# BpodFSM_r2_0.net
KiCad netlist of a schematic drawn in EAGLE
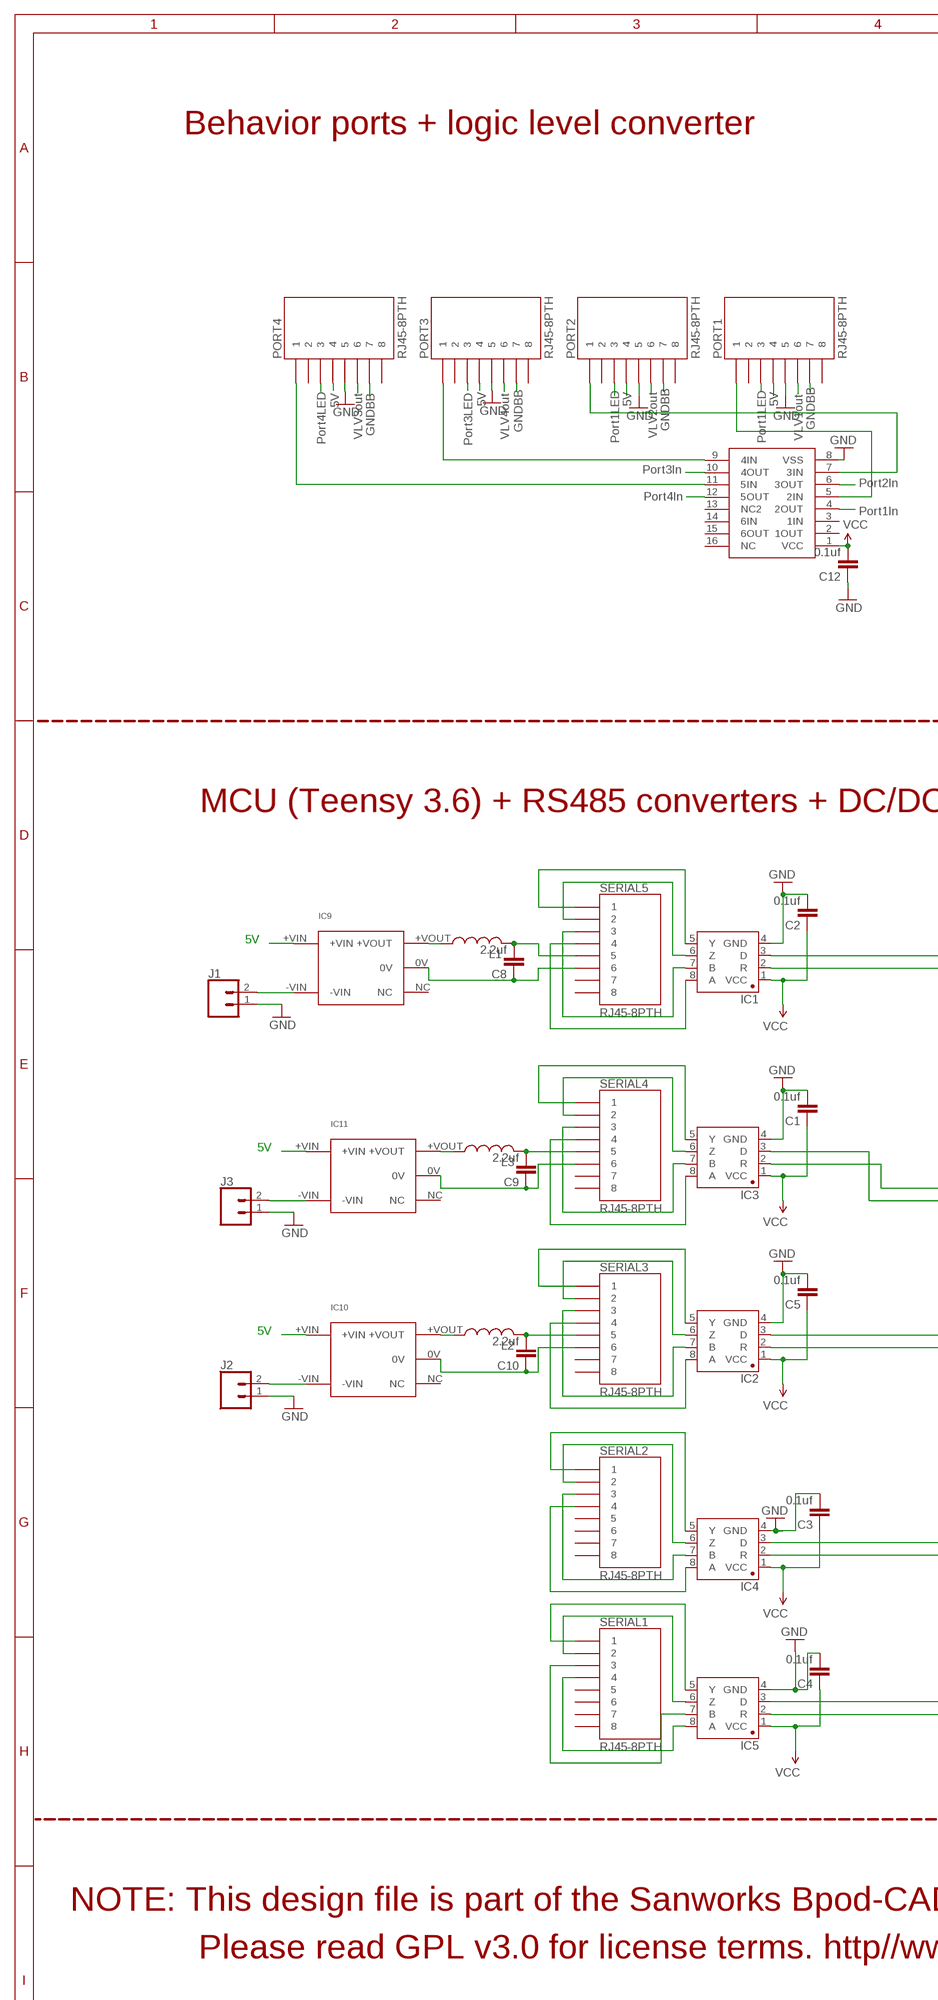
[diagram p0: schematic, sheet 1, part 1 of 2]
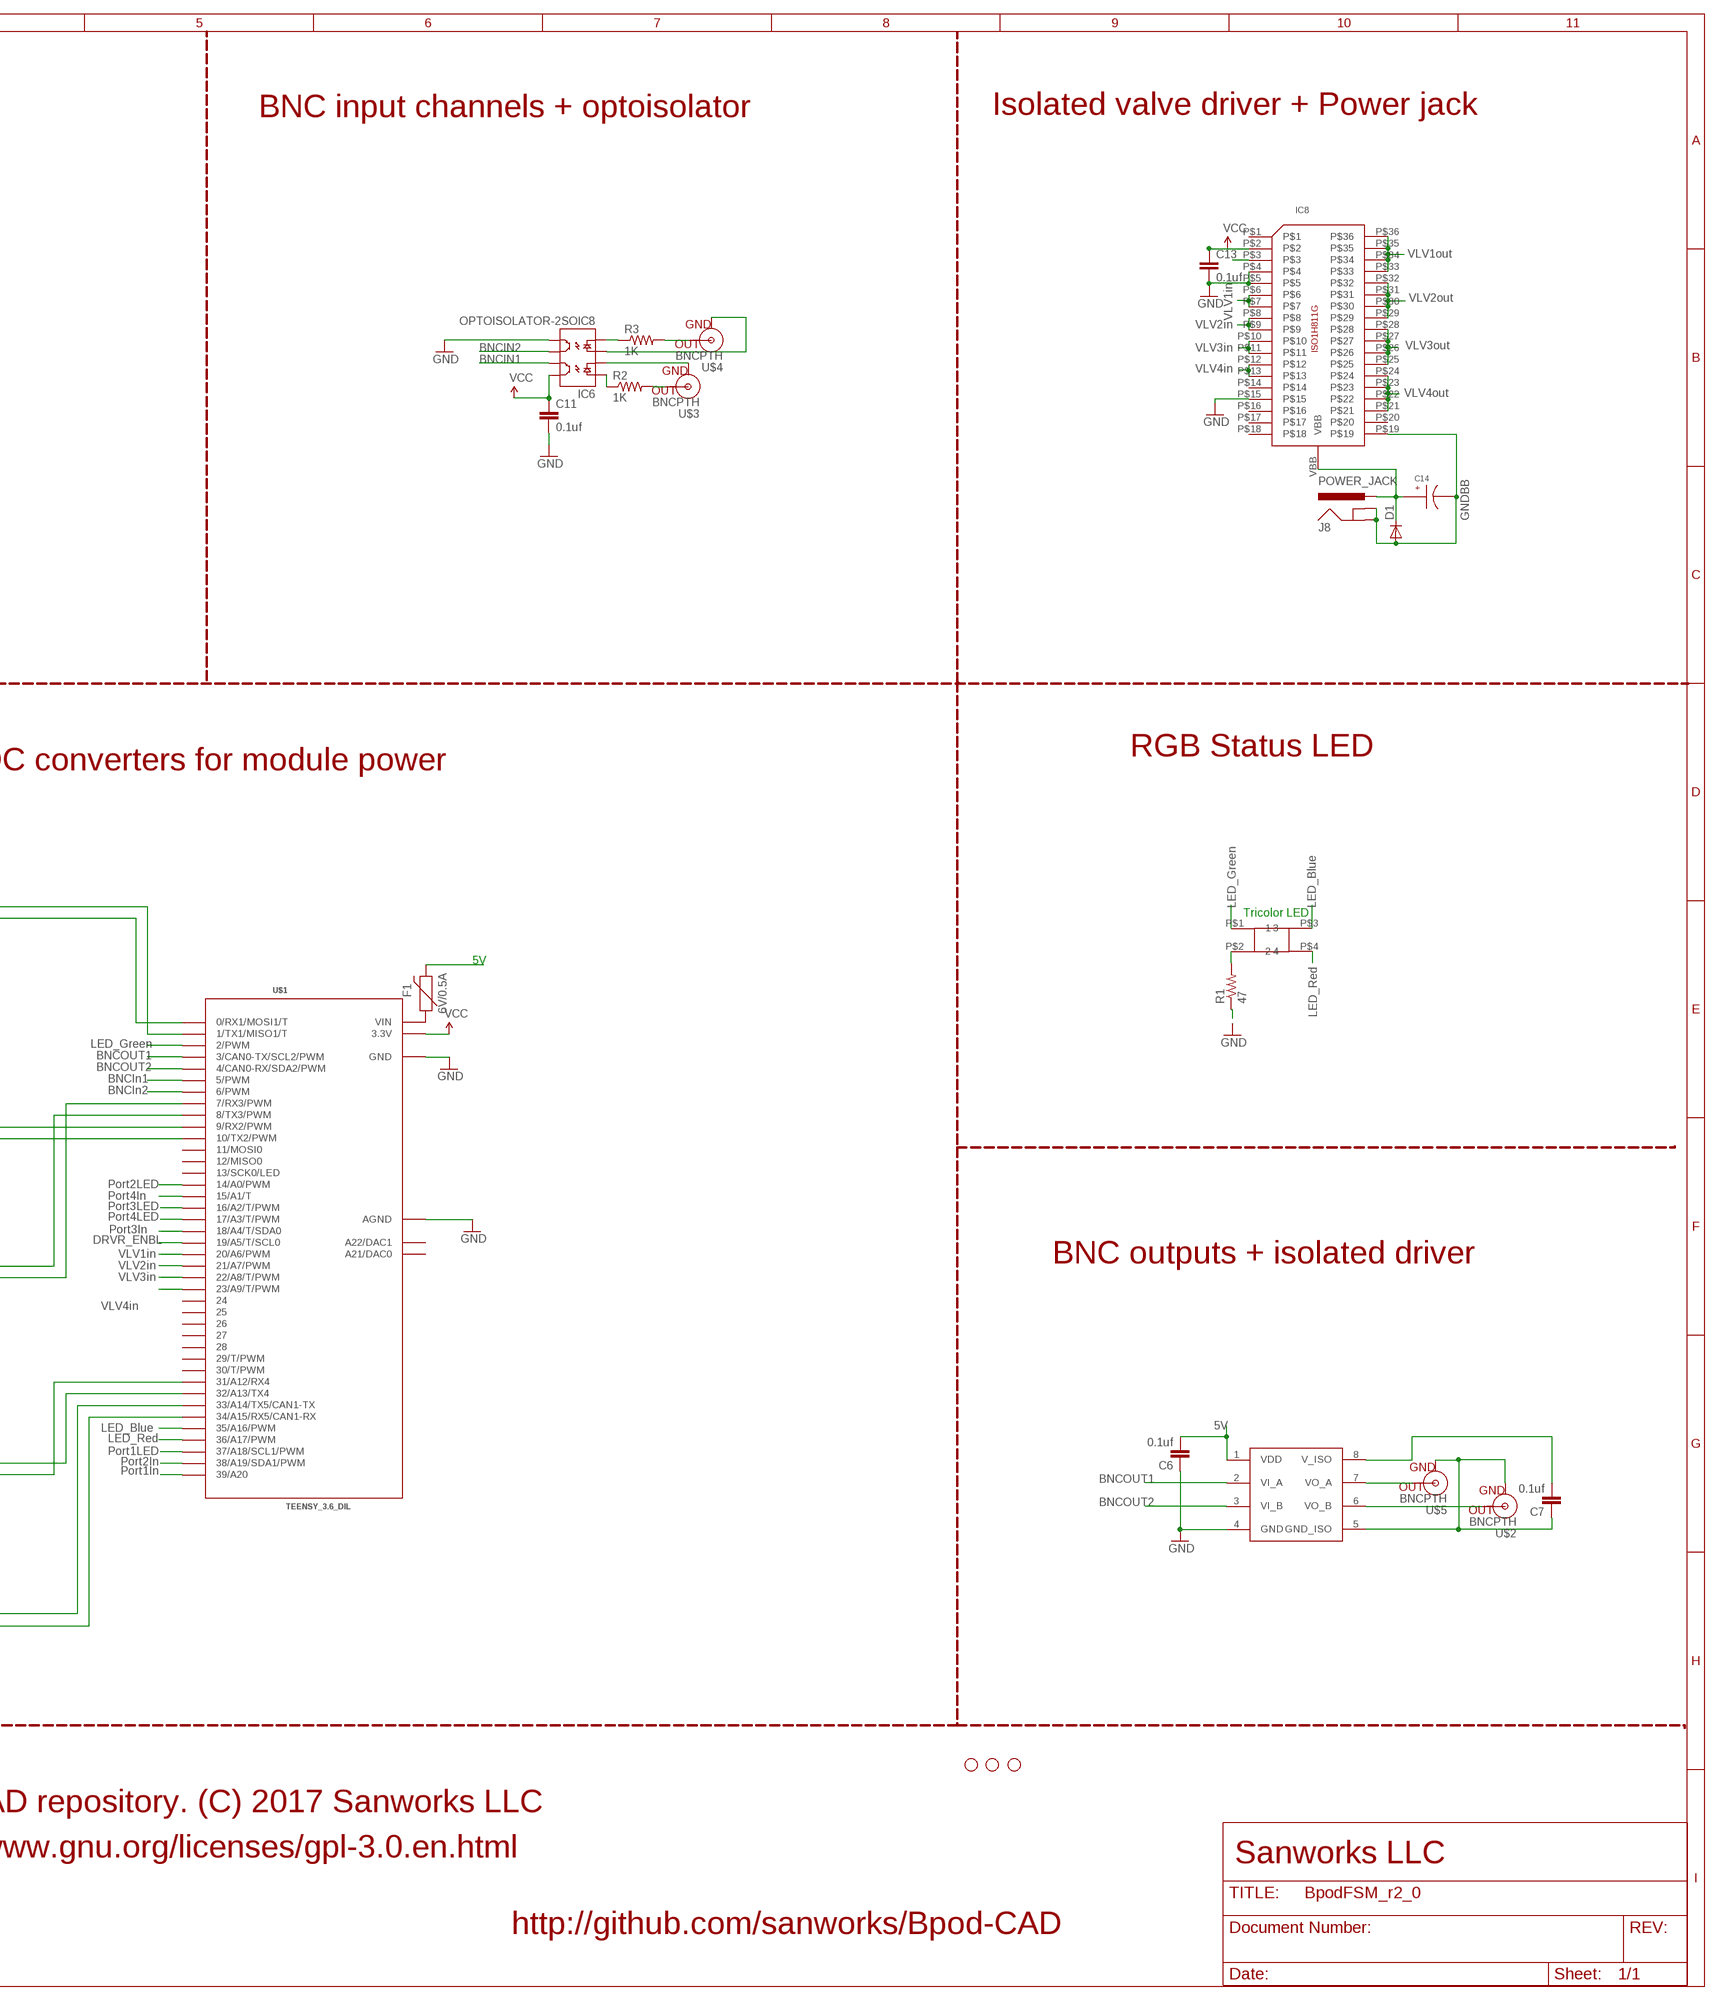
[diagram p1: schematic, sheet 1, part 2 of 2]

(export (version "E")
  (design (tool "Eeschema 10.0.6"))
  (components
    (comp (ref "C1")
      (value "0.1uf")
      (footprint "eagle-import:1206")
      (libsource (lib "eagle-import") (part "CAP1206"))
    )
    (comp (ref "C2")
      (value "0.1uf")
      (footprint "eagle-import:1206")
      (libsource (lib "eagle-import") (part "CAP1206"))
    )
    (comp (ref "C3")
      (value "0.1uf")
      (footprint "eagle-import:1206")
      (libsource (lib "eagle-import") (part "CAP1206"))
    )
    (comp (ref "C4")
      (value "0.1uf")
      (footprint "eagle-import:1206")
      (libsource (lib "eagle-import") (part "CAP1206"))
    )
    (comp (ref "C5")
      (value "0.1uf")
      (footprint "eagle-import:1206")
      (libsource (lib "eagle-import") (part "CAP1206"))
    )
    (comp (ref "C6")
      (value "0.1uf")
      (footprint "eagle-import:1206")
      (libsource (lib "eagle-import") (part "CAP1206"))
    )
    (comp (ref "C7")
      (value "0.1uf")
      (footprint "eagle-import:1206")
      (libsource (lib "eagle-import") (part "CAP1206"))
    )
    (comp (ref "C8")
      (value "2.2uf")
      (footprint "eagle-import:1206")
      (libsource (lib "eagle-import") (part "CAP1206"))
    )
    (comp (ref "C9")
      (value "2.2uf")
      (footprint "eagle-import:1206")
      (libsource (lib "eagle-import") (part "CAP1206"))
    )
    (comp (ref "C10")
      (value "2.2uf")
      (footprint "eagle-import:1206")
      (libsource (lib "eagle-import") (part "CAP1206"))
    )
    (comp (ref "C11")
      (value "0.1uf")
      (footprint "eagle-import:1206")
      (libsource (lib "eagle-import") (part "CAP1206"))
    )
    (comp (ref "C12")
      (value "0.1uf")
      (footprint "eagle-import:1206")
      (libsource (lib "eagle-import") (part "CAP1206"))
    )
    (comp (ref "C13")
      (value "0.1uf")
      (footprint "eagle-import:1206")
      (libsource (lib "eagle-import") (part "CAP1206"))
    )
    (comp (ref "C14")
      (value "EEE-FK1H100UR")
      (footprint "eagle-import:EEE-FK1H100UR")
      (libsource (lib "eagle-import") (part "EEE-FK1H100UR"))
    )
    (comp (ref "D1")
      (value "DIODE-DO214AA")
      (footprint "eagle-import:DO214AA")
      (libsource (lib "eagle-import") (part "DIODE-DO214AA"))
    )
    (comp (ref "F1")
      (value "6V/0.5A")
      (footprint "eagle-import:1206")
      (libsource (lib "eagle-import") (part "PPTC_HALF-AMP"))
    )
    (comp (ref "IC1")
      (value "SN65HVD31DR")
      (footprint "eagle-import:SO08")
      (libsource (lib "eagle-import") (part "SN65HVD31DR"))
    )
    (comp (ref "IC2")
      (value "SN65HVD31DR")
      (footprint "eagle-import:SO08")
      (libsource (lib "eagle-import") (part "SN65HVD31DR"))
    )
    (comp (ref "IC3")
      (value "SN65HVD31DR")
      (footprint "eagle-import:SO08")
      (libsource (lib "eagle-import") (part "SN65HVD31DR"))
    )
    (comp (ref "IC4")
      (value "SN65HVD31DR")
      (footprint "eagle-import:SO08")
      (libsource (lib "eagle-import") (part "SN65HVD31DR"))
    )
    (comp (ref "IC5")
      (value "SN65HVD31DR")
      (footprint "eagle-import:SO08")
      (libsource (lib "eagle-import") (part "SN65HVD31DR"))
    )
    (comp (ref "IC6")
      (value "OPTOISOLATOR-2SOIC8")
      (footprint "eagle-import:SO08-2")
      (libsource (lib "eagle-import") (part "OPTOISOLATOR-2SOIC8"))
    )
    (comp (ref "IC7")
      (value "ADUM5240")
      (footprint "eagle-import:SO08")
      (libsource (lib "eagle-import") (part "ADUM5240"))
    )
    (comp (ref "IC8")
      (value "ISO1H811G")
      (footprint "eagle-import:ISO1H811G")
      (libsource (lib "eagle-import") (part "ISO1H811G"))
    )
    (comp (ref "IC9")
      (value "MTU1D0505MC")
      (footprint "eagle-import:MTU1D0505MC")
      (libsource (lib "eagle-import") (part "MTU1D0505MC"))
    )
    (comp (ref "IC10")
      (value "MTU1D0505MC")
      (footprint "eagle-import:MTU1D0505MC")
      (libsource (lib "eagle-import") (part "MTU1D0505MC"))
    )
    (comp (ref "IC11")
      (value "MTU1D0505MC")
      (footprint "eagle-import:MTU1D0505MC")
      (libsource (lib "eagle-import") (part "MTU1D0505MC"))
    )
    (comp (ref "IC12")
      (value "CD4050")
      (footprint "eagle-import:SO16")
      (libsource (lib "eagle-import") (part "CD4050"))
    )
    (comp (ref "J1")
      (value "CONN_02")
      (footprint "eagle-import:1X02")
      (libsource (lib "eagle-import") (part "CONN_02"))
    )
    (comp (ref "J2")
      (value "CONN_02")
      (footprint "eagle-import:1X02")
      (libsource (lib "eagle-import") (part "CONN_02"))
    )
    (comp (ref "J3")
      (value "CONN_02")
      (footprint "eagle-import:1X02")
      (libsource (lib "eagle-import") (part "CONN_02"))
    )
    (comp (ref "J8")
      (value "POWER_JACK")
      (footprint "eagle-import:POWER_JACK_PTH")
      (libsource (lib "eagle-import") (part "POWER_JACK"))
    )
    (comp (ref "JP3")
      (value "STAND-OFF")
      (footprint "eagle-import:STAND-OFF")
      (libsource (lib "eagle-import") (part "STAND-OFF"))
    )
    (comp (ref "JP4")
      (value "STAND-OFF")
      (footprint "eagle-import:STAND-OFF")
      (libsource (lib "eagle-import") (part "STAND-OFF"))
    )
    (comp (ref "JP5")
      (value "STAND-OFF")
      (footprint "eagle-import:STAND-OFF")
      (libsource (lib "eagle-import") (part "STAND-OFF"))
    )
    (comp (ref "L1")
      (value "L-USL3225M")
      (footprint "eagle-import:L3225M")
      (libsource (lib "eagle-import") (part "L-USL3225M"))
    )
    (comp (ref "L2")
      (value "L-USL3225M")
      (footprint "eagle-import:L3225M")
      (libsource (lib "eagle-import") (part "L-USL3225M"))
    )
    (comp (ref "L3")
      (value "L-USL3225M")
      (footprint "eagle-import:L3225M")
      (libsource (lib "eagle-import") (part "L-USL3225M"))
    )
    (comp (ref "PORT1")
      (value "RJ45-8PTH")
      (footprint "eagle-import:RJ45-8")
      (libsource (lib "eagle-import") (part "RJ45-8PTH"))
    )
    (comp (ref "PORT2")
      (value "RJ45-8PTH")
      (footprint "eagle-import:RJ45-8")
      (libsource (lib "eagle-import") (part "RJ45-8PTH"))
    )
    (comp (ref "PORT3")
      (value "RJ45-8PTH")
      (footprint "eagle-import:RJ45-8")
      (libsource (lib "eagle-import") (part "RJ45-8PTH"))
    )
    (comp (ref "PORT4")
      (value "RJ45-8PTH")
      (footprint "eagle-import:RJ45-8")
      (libsource (lib "eagle-import") (part "RJ45-8PTH"))
    )
    (comp (ref "R1")
      (value "47")
      (footprint "eagle-import:1206")
      (libsource (lib "eagle-import") (part "RESISTOR1206"))
    )
    (comp (ref "R2")
      (value "1K")
      (footprint "eagle-import:1206")
      (libsource (lib "eagle-import") (part "SparkFun-Resistors_RESISTOR1206"))
    )
    (comp (ref "R3")
      (value "1K")
      (footprint "eagle-import:1206")
      (libsource (lib "eagle-import") (part "SparkFun-Resistors_RESISTOR1206"))
    )
    (comp (ref "SERIAL1")
      (value "RJ45-8PTH")
      (footprint "eagle-import:RJ45-8")
      (libsource (lib "eagle-import") (part "RJ45-8PTH"))
    )
    (comp (ref "SERIAL2")
      (value "RJ45-8PTH")
      (footprint "eagle-import:RJ45-8")
      (libsource (lib "eagle-import") (part "RJ45-8PTH"))
    )
    (comp (ref "SERIAL3")
      (value "RJ45-8PTH")
      (footprint "eagle-import:RJ45-8")
      (libsource (lib "eagle-import") (part "RJ45-8PTH"))
    )
    (comp (ref "SERIAL4")
      (value "RJ45-8PTH")
      (footprint "eagle-import:RJ45-8")
      (libsource (lib "eagle-import") (part "RJ45-8PTH"))
    )
    (comp (ref "SERIAL5")
      (value "RJ45-8PTH")
      (footprint "eagle-import:RJ45-8")
      (libsource (lib "eagle-import") (part "RJ45-8PTH"))
    )
    (comp (ref "U$1")
      (value "TEENSY_3.6_DIL")
      (footprint "eagle-import:TEENSY_3.6_DIL")
      (libsource (lib "eagle-import") (part "TEENSY_3.6_DIL"))
    )
    (comp (ref "U$2")
      (value "BNCPTH")
      (footprint "eagle-import:BNC")
      (libsource (lib "eagle-import") (part "BNCPTH"))
    )
    (comp (ref "U$3")
      (value "BNCPTH")
      (footprint "eagle-import:BNC")
      (libsource (lib "eagle-import") (part "BNCPTH"))
    )
    (comp (ref "U$4")
      (value "BNCPTH")
      (footprint "eagle-import:BNC")
      (libsource (lib "eagle-import") (part "BNCPTH"))
    )
    (comp (ref "U$5")
      (value "BNCPTH")
      (footprint "eagle-import:BNC")
      (libsource (lib "eagle-import") (part "BNCPTH"))
    )
    (comp (ref "U$8")
      (value "SQUARE_TRICOLOR_LED")
      (footprint "eagle-import:SQUARE_TRICOLOR_LED")
      (libsource (lib "eagle-import") (part "SQUARE_TRICOLOR_LED"))
    )
  )
  (nets
    (net (code "1") (name "/5V") (class "Default")
      (node (ref "C6") (pin "2") (pinfunction "2_2") (pintype "passive"))
      (node (ref "F1") (pin "2") (pinfunction "2_2") (pintype "bidirectional"))
      (node (ref "IC10") (pin "+VIN") (pinfunction "+VIN_+VIN") (pintype "bidirectional"))
      (node (ref "IC11") (pin "+VIN") (pinfunction "+VIN_+VIN") (pintype "bidirectional"))
      (node (ref "IC7") (pin "1") (pinfunction "VDD_1") (pintype "bidirectional"))
      (node (ref "IC9") (pin "+VIN") (pinfunction "+VIN_+VIN") (pintype "bidirectional"))
      (node (ref "PORT1") (pin "4") (pinfunction "4_4") (pintype "bidirectional"))
      (node (ref "PORT2") (pin "4") (pinfunction "4_4") (pintype "bidirectional"))
      (node (ref "PORT3") (pin "4") (pinfunction "4_4") (pintype "bidirectional"))
      (node (ref "PORT4") (pin "4") (pinfunction "4_4") (pintype "bidirectional"))
    )
    (net (code "2") (name "/BNCIN1") (class "Default")
      (node (ref "IC6") (pin "7") (pinfunction "EM1_7") (pintype "bidirectional"))
      (node (ref "U$1") (pin "6") (pinfunction "6/PWM_6") (pintype "bidirectional"))
    )
    (net (code "3") (name "/BNCIN2") (class "Default")
      (node (ref "IC6") (pin "6") (pinfunction "CL2_6") (pintype "bidirectional"))
      (node (ref "U$1") (pin "5") (pinfunction "5/PWM_5") (pintype "bidirectional"))
    )
    (net (code "4") (name "/BNCOUT1") (class "Default")
      (node (ref "IC7") (pin "3") (pinfunction "VI_B_3") (pintype "bidirectional"))
      (node (ref "U$1") (pin "4") (pinfunction "4/CAN0-RX/SDA2/PWM_4") (pintype "bidirectional"))
    )
    (net (code "5") (name "/BNCOUT2") (class "Default")
      (node (ref "IC7") (pin "2") (pinfunction "VI_A_2") (pintype "bidirectional"))
      (node (ref "U$1") (pin "3") (pinfunction "3/CAN0-TX/SCL2/PWM_3") (pintype "bidirectional"))
    )
    (net (code "6") (name "/DRVR_ENBL") (class "Default")
      (node (ref "IC8") (pin "P$3") (pinfunction "P$3_P$3") (pintype "bidirectional"))
      (node (ref "U$1") (pin "19/A5") (pinfunction "19/A5/T/SCL0_19/A5") (pintype "bidirectional"))
    )
    (net (code "7") (name "/GNDBB") (class "Default")
      (node (ref "C14") (pin "CATHODE") (pinfunction "CATHODE_CATHODE") (pintype "bidirectional"))
      (node (ref "D1") (pin "A") (pinfunction "A_A") (pintype "passive"))
      (node (ref "IC8") (pin "P$19") (pinfunction "P$19_P$19") (pintype "bidirectional"))
      (node (ref "J8") (pin "GND") (pinfunction "GND_GND") (pintype "bidirectional"))
      (node (ref "J8") (pin "GNDBREAK") (pinfunction "GNDBREAK_GNDBREAK") (pintype "bidirectional"))
      (node (ref "PORT1") (pin "7") (pinfunction "7_7") (pintype "bidirectional"))
      (node (ref "PORT2") (pin "7") (pinfunction "7_7") (pintype "bidirectional"))
      (node (ref "PORT3") (pin "7") (pinfunction "7_7") (pintype "bidirectional"))
      (node (ref "PORT4") (pin "7") (pinfunction "7_7") (pintype "bidirectional"))
    )
    (net (code "8") (name "/LED_BLUE") (class "Default")
      (node (ref "U$1") (pin "35/A16") (pinfunction "35/A16/PWM_35/A16") (pintype "bidirectional"))
      (node (ref "U$8") (pin "P$3") (pinfunction "3_P$3") (pintype "bidirectional"))
    )
    (net (code "9") (name "/LED_GREEN") (class "Default")
      (node (ref "U$1") (pin "2") (pinfunction "2/PWM_2") (pintype "bidirectional"))
      (node (ref "U$8") (pin "P$1") (pinfunction "1_P$1") (pintype "bidirectional"))
    )
    (net (code "10") (name "/LED_RED") (class "Default")
      (node (ref "U$1") (pin "36/A17") (pinfunction "36/A17/PWM_36/A17") (pintype "bidirectional"))
      (node (ref "U$8") (pin "P$4") (pinfunction "4_P$4") (pintype "bidirectional"))
    )
    (net (code "11") (name "/PORT1IN") (class "Default")
      (node (ref "IC12") (pin "4") (pinfunction "2OUT_4") (pintype "bidirectional"))
      (node (ref "U$1") (pin "39/A20") (pinfunction "39/A20_39/A20") (pintype "bidirectional"))
    )
    (net (code "12") (name "/PORT1LED") (class "Default")
      (node (ref "PORT1") (pin "3") (pinfunction "3_3") (pintype "bidirectional"))
      (node (ref "U$1") (pin "37/A18") (pinfunction "37/A18/SCL1/PWM_37/A18") (pintype "bidirectional"))
    )
    (net (code "13") (name "/PORT2IN") (class "Default")
      (node (ref "IC12") (pin "6") (pinfunction "3OUT_6") (pintype "bidirectional"))
      (node (ref "U$1") (pin "38/A19") (pinfunction "38/A19/SDA1/PWM_38/A19") (pintype "bidirectional"))
    )
    (net (code "14") (name "/PORT2LED") (class "Default")
      (node (ref "PORT2") (pin "3") (pinfunction "3_3") (pintype "bidirectional"))
      (node (ref "U$1") (pin "14/A0") (pinfunction "14/A0/PWM_14/A0") (pintype "bidirectional"))
    )
    (net (code "15") (name "/PORT3IN") (class "Default")
      (node (ref "IC12") (pin "10") (pinfunction "4OUT_10") (pintype "bidirectional"))
      (node (ref "U$1") (pin "18/A4") (pinfunction "18/A4/T/SDA0_18/A4") (pintype "bidirectional"))
    )
    (net (code "16") (name "/PORT3LED") (class "Default")
      (node (ref "PORT3") (pin "3") (pinfunction "3_3") (pintype "bidirectional"))
      (node (ref "U$1") (pin "16/A2") (pinfunction "16/A2/T/PWM_16/A2") (pintype "bidirectional"))
    )
    (net (code "17") (name "/PORT4IN") (class "Default")
      (node (ref "IC12") (pin "12") (pinfunction "5OUT_12") (pintype "bidirectional"))
      (node (ref "U$1") (pin "15/A1") (pinfunction "15/A1/T_15/A1") (pintype "bidirectional"))
    )
    (net (code "18") (name "/PORT4LED") (class "Default")
      (node (ref "PORT4") (pin "3") (pinfunction "3_3") (pintype "bidirectional"))
      (node (ref "U$1") (pin "17/A3") (pinfunction "17/A3/T/PWM_17/A3") (pintype "bidirectional"))
    )
    (net (code "19") (name "/VLV1IN") (class "Default")
      (node (ref "IC8") (pin "P$6") (pinfunction "P$6_P$6") (pintype "bidirectional"))
      (node (ref "IC8") (pin "P$7") (pinfunction "P$7_P$7") (pintype "bidirectional"))
      (node (ref "U$1") (pin "23/A9") (pinfunction "23/A9/T/PWM_23/A9") (pintype "bidirectional"))
    )
    (net (code "20") (name "/VLV1OUT") (class "Default")
      (node (ref "IC8") (pin "P$33") (pinfunction "P$33_P$33") (pintype "bidirectional"))
      (node (ref "IC8") (pin "P$34") (pinfunction "P$34_P$34") (pintype "bidirectional"))
      (node (ref "IC8") (pin "P$35") (pinfunction "P$35_P$35") (pintype "bidirectional"))
      (node (ref "IC8") (pin "P$36") (pinfunction "P$36_P$36") (pintype "bidirectional"))
      (node (ref "PORT1") (pin "6") (pinfunction "6_6") (pintype "bidirectional"))
    )
    (net (code "21") (name "/VLV2IN") (class "Default")
      (node (ref "IC8") (pin "P$8") (pinfunction "P$8_P$8") (pintype "bidirectional"))
      (node (ref "IC8") (pin "P$9") (pinfunction "P$9_P$9") (pintype "bidirectional"))
      (node (ref "U$1") (pin "22/A8") (pinfunction "22/A8/T/PWM_22/A8") (pintype "bidirectional"))
    )
    (net (code "22") (name "/VLV2OUT") (class "Default")
      (node (ref "IC8") (pin "P$29") (pinfunction "P$29_P$29") (pintype "bidirectional"))
      (node (ref "IC8") (pin "P$30") (pinfunction "P$30_P$30") (pintype "bidirectional"))
      (node (ref "IC8") (pin "P$31") (pinfunction "P$31_P$31") (pintype "bidirectional"))
      (node (ref "IC8") (pin "P$32") (pinfunction "P$32_P$32") (pintype "bidirectional"))
      (node (ref "PORT2") (pin "6") (pinfunction "6_6") (pintype "bidirectional"))
    )
    (net (code "23") (name "/VLV3IN") (class "Default")
      (node (ref "IC8") (pin "P$12") (pinfunction "P$12_P$12") (pintype "bidirectional"))
      (node (ref "IC8") (pin "P$13") (pinfunction "P$13_P$13") (pintype "bidirectional"))
      (node (ref "U$1") (pin "20/A6") (pinfunction "20/A6/PWM_20/A6") (pintype "bidirectional"))
    )
    (net (code "24") (name "/VLV3OUT") (class "Default")
      (node (ref "IC8") (pin "P$21") (pinfunction "P$21_P$21") (pintype "bidirectional"))
      (node (ref "IC8") (pin "P$22") (pinfunction "P$22_P$22") (pintype "bidirectional"))
      (node (ref "IC8") (pin "P$23") (pinfunction "P$23_P$23") (pintype "bidirectional"))
      (node (ref "IC8") (pin "P$24") (pinfunction "P$24_P$24") (pintype "bidirectional"))
      (node (ref "PORT3") (pin "6") (pinfunction "6_6") (pintype "bidirectional"))
    )
    (net (code "25") (name "/VLV4IN") (class "Default")
      (node (ref "IC8") (pin "P$10") (pinfunction "P$10_P$10") (pintype "bidirectional"))
      (node (ref "IC8") (pin "P$11") (pinfunction "P$11_P$11") (pintype "bidirectional"))
      (node (ref "U$1") (pin "21/A7") (pinfunction "21/A7/PWM_21/A7") (pintype "bidirectional"))
    )
    (net (code "26") (name "/VLV4OUT") (class "Default")
      (node (ref "IC8") (pin "P$25") (pinfunction "P$25_P$25") (pintype "bidirectional"))
      (node (ref "IC8") (pin "P$26") (pinfunction "P$26_P$26") (pintype "bidirectional"))
      (node (ref "IC8") (pin "P$27") (pinfunction "P$27_P$27") (pintype "bidirectional"))
      (node (ref "IC8") (pin "P$28") (pinfunction "P$28_P$28") (pintype "bidirectional"))
      (node (ref "PORT4") (pin "6") (pinfunction "6_6") (pintype "bidirectional"))
    )
    (net (code "27") (name "GND") (class "Default")
      (node (ref "C1") (pin "2") (pinfunction "2_2") (pintype "passive"))
      (node (ref "C11") (pin "2") (pinfunction "2_2") (pintype "passive"))
      (node (ref "C12") (pin "1") (pinfunction "1_1") (pintype "passive"))
      (node (ref "C13") (pin "2") (pinfunction "2_2") (pintype "passive"))
      (node (ref "C2") (pin "2") (pinfunction "2_2") (pintype "passive"))
      (node (ref "C3") (pin "2") (pinfunction "2_2") (pintype "passive"))
      (node (ref "C4") (pin "2") (pinfunction "2_2") (pintype "passive"))
      (node (ref "C5") (pin "2") (pinfunction "2_2") (pintype "passive"))
      (node (ref "C6") (pin "1") (pinfunction "1_1") (pintype "passive"))
      (node (ref "IC1") (pin "4") (pinfunction "GND_4") (pintype "bidirectional"))
      (node (ref "IC12") (pin "8") (pinfunction "VSS_8") (pintype "bidirectional"))
      (node (ref "IC2") (pin "4") (pinfunction "GND_4") (pintype "bidirectional"))
      (node (ref "IC3") (pin "4") (pinfunction "GND_4") (pintype "bidirectional"))
      (node (ref "IC4") (pin "4") (pinfunction "GND_4") (pintype "bidirectional"))
      (node (ref "IC5") (pin "4") (pinfunction "GND_4") (pintype "bidirectional"))
      (node (ref "IC6") (pin "5") (pinfunction "EM2_5") (pintype "bidirectional"))
      (node (ref "IC7") (pin "4") (pinfunction "GND_4") (pintype "bidirectional"))
      (node (ref "IC8") (pin "P$15") (pinfunction "P$15_P$15") (pintype "bidirectional"))
      (node (ref "IC8") (pin "P$4") (pinfunction "P$4_P$4") (pintype "bidirectional"))
      (node (ref "IC8") (pin "P$5") (pinfunction "P$5_P$5") (pintype "bidirectional"))
      (node (ref "J1") (pin "1") (pinfunction "1_1") (pintype "passive"))
      (node (ref "J2") (pin "1") (pinfunction "1_1") (pintype "passive"))
      (node (ref "J3") (pin "1") (pinfunction "1_1") (pintype "passive"))
      (node (ref "PORT1") (pin "5") (pinfunction "5_5") (pintype "bidirectional"))
      (node (ref "PORT2") (pin "5") (pinfunction "5_5") (pintype "bidirectional"))
      (node (ref "PORT3") (pin "5") (pinfunction "5_5") (pintype "bidirectional"))
      (node (ref "PORT4") (pin "5") (pinfunction "5_5") (pintype "bidirectional"))
      (node (ref "R1") (pin "1") (pinfunction "1_1") (pintype "passive"))
      (node (ref "U$1") (pin "AGND") (pinfunction "AGND_AGND") (pintype "power_in"))
      (node (ref "U$1") (pin "GND") (pinfunction "GND_GND") (pintype "power_in"))
      (node (ref "U$1") (pin "GND1") (pinfunction "GND_GND1") (pintype "power_in"))
    )
    (net (code "28") (name "Net-(C8-Pad1)") (class "Default")
      (node (ref "C8") (pin "1") (pinfunction "1_1") (pintype "passive"))
      (node (ref "IC9") (pin "0V") (pinfunction "0V_0V") (pintype "bidirectional"))
      (node (ref "SERIAL5") (pin "6") (pinfunction "6_6") (pintype "bidirectional"))
    )
    (net (code "29") (name "Net-(C8-Pad2)") (class "Default")
      (node (ref "C8") (pin "2") (pinfunction "2_2") (pintype "passive"))
      (node (ref "L1") (pin "2") (pinfunction "2_2") (pintype "passive"))
      (node (ref "SERIAL5") (pin "5") (pinfunction "5_5") (pintype "bidirectional"))
    )
    (net (code "30") (name "Net-(C9-Pad1)") (class "Default")
      (node (ref "C9") (pin "1") (pinfunction "1_1") (pintype "passive"))
      (node (ref "IC11") (pin "0V") (pinfunction "0V_0V") (pintype "bidirectional"))
      (node (ref "SERIAL4") (pin "6") (pinfunction "6_6") (pintype "bidirectional"))
    )
    (net (code "31") (name "Net-(C9-Pad2)") (class "Default")
      (node (ref "C9") (pin "2") (pinfunction "2_2") (pintype "passive"))
      (node (ref "L3") (pin "2") (pinfunction "2_2") (pintype "passive"))
      (node (ref "SERIAL4") (pin "5") (pinfunction "5_5") (pintype "bidirectional"))
    )
    (net (code "32") (name "Net-(C10-Pad1)") (class "Default")
      (node (ref "C10") (pin "1") (pinfunction "1_1") (pintype "passive"))
      (node (ref "IC10") (pin "0V") (pinfunction "0V_0V") (pintype "bidirectional"))
      (node (ref "SERIAL3") (pin "6") (pinfunction "6_6") (pintype "bidirectional"))
    )
    (net (code "33") (name "Net-(C10-Pad2)") (class "Default")
      (node (ref "C10") (pin "2") (pinfunction "2_2") (pintype "passive"))
      (node (ref "L2") (pin "2") (pinfunction "2_2") (pintype "passive"))
      (node (ref "SERIAL3") (pin "5") (pinfunction "5_5") (pintype "bidirectional"))
    )
    (net (code "34") (name "Net-(C14-PadANODE)") (class "Default")
      (node (ref "C14") (pin "ANODE") (pinfunction "ANODE_ANODE") (pintype "bidirectional"))
      (node (ref "D1") (pin "C") (pinfunction "C_C") (pintype "passive"))
      (node (ref "IC8") (pin "VBB") (pinfunction "VBB_VBB") (pintype "bidirectional"))
      (node (ref "J8") (pin "PWR") (pinfunction "PWR_PWR") (pintype "bidirectional"))
    )
    (net (code "35") (name "Net-(F1-Pad1)") (class "Default")
      (node (ref "F1") (pin "1") (pinfunction "1_1") (pintype "bidirectional"))
      (node (ref "U$1") (pin "VIN") (pinfunction "VIN_VIN") (pintype "power_in"))
    )
    (net (code "36") (name "Net-(IC1-A)") (class "Default")
      (node (ref "IC1") (pin "8") (pinfunction "A_8") (pintype "bidirectional"))
      (node (ref "SERIAL5") (pin "4") (pinfunction "4_4") (pintype "bidirectional"))
    )
    (net (code "37") (name "Net-(IC1-B)") (class "Default")
      (node (ref "IC1") (pin "7") (pinfunction "B_7") (pintype "bidirectional"))
      (node (ref "SERIAL5") (pin "3") (pinfunction "3_3") (pintype "bidirectional"))
    )
    (net (code "38") (name "Net-(IC1-D)") (class "Default")
      (node (ref "IC1") (pin "3") (pinfunction "D_3") (pintype "bidirectional"))
      (node (ref "U$1") (pin "1") (pinfunction "1/TX1/MISO1/T_1") (pintype "bidirectional"))
    )
    (net (code "39") (name "Net-(IC1-R)") (class "Default")
      (node (ref "IC1") (pin "2") (pinfunction "R_2") (pintype "bidirectional"))
      (node (ref "U$1") (pin "0") (pinfunction "0/RX1/MOSI1/T_0") (pintype "bidirectional"))
    )
    (net (code "40") (name "Net-(IC1-Y)") (class "Default")
      (node (ref "IC1") (pin "5") (pinfunction "Y_5") (pintype "bidirectional"))
      (node (ref "SERIAL5") (pin "1") (pinfunction "1_1") (pintype "bidirectional"))
    )
    (net (code "41") (name "Net-(IC1-Z)") (class "Default")
      (node (ref "IC1") (pin "6") (pinfunction "Z_6") (pintype "bidirectional"))
      (node (ref "SERIAL5") (pin "2") (pinfunction "2_2") (pintype "bidirectional"))
    )
    (net (code "42") (name "Net-(IC2-A)") (class "Default")
      (node (ref "IC2") (pin "8") (pinfunction "A_8") (pintype "bidirectional"))
      (node (ref "SERIAL3") (pin "4") (pinfunction "4_4") (pintype "bidirectional"))
    )
    (net (code "43") (name "Net-(IC2-B)") (class "Default")
      (node (ref "IC2") (pin "7") (pinfunction "B_7") (pintype "bidirectional"))
      (node (ref "SERIAL3") (pin "3") (pinfunction "3_3") (pintype "bidirectional"))
    )
    (net (code "44") (name "Net-(IC2-D)") (class "Default")
      (node (ref "IC2") (pin "3") (pinfunction "D_3") (pintype "bidirectional"))
      (node (ref "U$1") (pin "8") (pinfunction "8/TX3/PWM_8") (pintype "bidirectional"))
    )
    (net (code "45") (name "Net-(IC2-R)") (class "Default")
      (node (ref "IC2") (pin "2") (pinfunction "R_2") (pintype "bidirectional"))
      (node (ref "U$1") (pin "7") (pinfunction "7/RX3/PWM_7") (pintype "bidirectional"))
    )
    (net (code "46") (name "Net-(IC2-Y)") (class "Default")
      (node (ref "IC2") (pin "5") (pinfunction "Y_5") (pintype "bidirectional"))
      (node (ref "SERIAL3") (pin "1") (pinfunction "1_1") (pintype "bidirectional"))
    )
    (net (code "47") (name "Net-(IC2-Z)") (class "Default")
      (node (ref "IC2") (pin "6") (pinfunction "Z_6") (pintype "bidirectional"))
      (node (ref "SERIAL3") (pin "2") (pinfunction "2_2") (pintype "bidirectional"))
    )
    (net (code "48") (name "Net-(IC3-A)") (class "Default")
      (node (ref "IC3") (pin "8") (pinfunction "A_8") (pintype "bidirectional"))
      (node (ref "SERIAL4") (pin "4") (pinfunction "4_4") (pintype "bidirectional"))
    )
    (net (code "49") (name "Net-(IC3-B)") (class "Default")
      (node (ref "IC3") (pin "7") (pinfunction "B_7") (pintype "bidirectional"))
      (node (ref "SERIAL4") (pin "3") (pinfunction "3_3") (pintype "bidirectional"))
    )
    (net (code "50") (name "Net-(IC3-D)") (class "Default")
      (node (ref "IC3") (pin "3") (pinfunction "D_3") (pintype "bidirectional"))
      (node (ref "U$1") (pin "10") (pinfunction "10/TX2/PWM_10") (pintype "bidirectional"))
    )
    (net (code "51") (name "Net-(IC3-R)") (class "Default")
      (node (ref "IC3") (pin "2") (pinfunction "R_2") (pintype "bidirectional"))
      (node (ref "U$1") (pin "9") (pinfunction "9/RX2/PWM_9") (pintype "bidirectional"))
    )
    (net (code "52") (name "Net-(IC3-Y)") (class "Default")
      (node (ref "IC3") (pin "5") (pinfunction "Y_5") (pintype "bidirectional"))
      (node (ref "SERIAL4") (pin "1") (pinfunction "1_1") (pintype "bidirectional"))
    )
    (net (code "53") (name "Net-(IC3-Z)") (class "Default")
      (node (ref "IC3") (pin "6") (pinfunction "Z_6") (pintype "bidirectional"))
      (node (ref "SERIAL4") (pin "2") (pinfunction "2_2") (pintype "bidirectional"))
    )
    (net (code "54") (name "Net-(IC4-A)") (class "Default")
      (node (ref "IC4") (pin "8") (pinfunction "A_8") (pintype "bidirectional"))
      (node (ref "SERIAL2") (pin "4") (pinfunction "4_4") (pintype "bidirectional"))
    )
    (net (code "55") (name "Net-(IC4-B)") (class "Default")
      (node (ref "IC4") (pin "7") (pinfunction "B_7") (pintype "bidirectional"))
      (node (ref "SERIAL2") (pin "3") (pinfunction "3_3") (pintype "bidirectional"))
    )
    (net (code "56") (name "Net-(IC4-D)") (class "Default")
      (node (ref "IC4") (pin "3") (pinfunction "D_3") (pintype "bidirectional"))
      (node (ref "U$1") (pin "32/A13") (pinfunction "32/A13/TX4_32/A13") (pintype "bidirectional"))
    )
    (net (code "57") (name "Net-(IC4-R)") (class "Default")
      (node (ref "IC4") (pin "2") (pinfunction "R_2") (pintype "bidirectional"))
      (node (ref "U$1") (pin "31/A12") (pinfunction "31/A12/RX4_31/A12") (pintype "bidirectional"))
    )
    (net (code "58") (name "Net-(IC4-Y)") (class "Default")
      (node (ref "IC4") (pin "5") (pinfunction "Y_5") (pintype "bidirectional"))
      (node (ref "SERIAL2") (pin "1") (pinfunction "1_1") (pintype "bidirectional"))
    )
    (net (code "59") (name "Net-(IC4-Z)") (class "Default")
      (node (ref "IC4") (pin "6") (pinfunction "Z_6") (pintype "bidirectional"))
      (node (ref "SERIAL2") (pin "2") (pinfunction "2_2") (pintype "bidirectional"))
    )
    (net (code "60") (name "Net-(IC5-A)") (class "Default")
      (node (ref "IC5") (pin "8") (pinfunction "A_8") (pintype "bidirectional"))
      (node (ref "SERIAL1") (pin "4") (pinfunction "4_4") (pintype "bidirectional"))
    )
    (net (code "61") (name "Net-(IC5-B)") (class "Default")
      (node (ref "IC5") (pin "7") (pinfunction "B_7") (pintype "bidirectional"))
      (node (ref "SERIAL1") (pin "3") (pinfunction "3_3") (pintype "bidirectional"))
    )
    (net (code "62") (name "Net-(IC5-D)") (class "Default")
      (node (ref "IC5") (pin "3") (pinfunction "D_3") (pintype "bidirectional"))
      (node (ref "U$1") (pin "33/A14") (pinfunction "33/A14/TX5/CAN1-TX_33/A14") (pintype "bidirectional"))
    )
    (net (code "63") (name "Net-(IC5-R)") (class "Default")
      (node (ref "IC5") (pin "2") (pinfunction "R_2") (pintype "bidirectional"))
      (node (ref "U$1") (pin "34/A15") (pinfunction "34/A15/RX5/CAN1-RX_34/A15") (pintype "bidirectional"))
    )
    (net (code "64") (name "Net-(IC5-Y)") (class "Default")
      (node (ref "IC5") (pin "5") (pinfunction "Y_5") (pintype "bidirectional"))
      (node (ref "SERIAL1") (pin "1") (pinfunction "1_1") (pintype "bidirectional"))
    )
    (net (code "65") (name "Net-(IC5-Z)") (class "Default")
      (node (ref "IC5") (pin "6") (pinfunction "Z_6") (pintype "bidirectional"))
      (node (ref "SERIAL1") (pin "2") (pinfunction "2_2") (pintype "bidirectional"))
    )
    (net (code "66") (name "Net-(IC6-A1)") (class "Default")
      (node (ref "IC6") (pin "1") (pinfunction "A1_1") (pintype "bidirectional"))
      (node (ref "R2") (pin "1") (pinfunction "1_1") (pintype "passive"))
    )
    (net (code "67") (name "Net-(IC6-A2)") (class "Default")
      (node (ref "IC6") (pin "3") (pinfunction "A2_3") (pintype "bidirectional"))
      (node (ref "U$4") (pin "GND") (pinfunction "GND_GND") (pintype "bidirectional"))
    )
    (net (code "68") (name "Net-(IC6-C1)") (class "Default")
      (node (ref "IC6") (pin "2") (pinfunction "C1_2") (pintype "bidirectional"))
      (node (ref "U$3") (pin "GND") (pinfunction "GND_GND") (pintype "bidirectional"))
    )
    (net (code "69") (name "Net-(IC6-C2)") (class "Default")
      (node (ref "IC6") (pin "4") (pinfunction "C2_4") (pintype "bidirectional"))
      (node (ref "R3") (pin "1") (pinfunction "1_1") (pintype "passive"))
    )
    (net (code "70") (name "Net-(IC7-GND_ISO)") (class "Default")
      (node (ref "C7") (pin "1") (pinfunction "1_1") (pintype "passive"))
      (node (ref "IC7") (pin "5") (pinfunction "GND_ISO_5") (pintype "bidirectional"))
      (node (ref "U$2") (pin "GND") (pinfunction "GND_GND") (pintype "bidirectional"))
      (node (ref "U$5") (pin "GND") (pinfunction "GND_GND") (pintype "bidirectional"))
    )
    (net (code "71") (name "Net-(IC7-VO_A)") (class "Default")
      (node (ref "IC7") (pin "7") (pinfunction "VO_A_7") (pintype "bidirectional"))
      (node (ref "U$5") (pin "S") (pinfunction "OUT_S") (pintype "bidirectional"))
    )
    (net (code "72") (name "Net-(IC7-VO_B)") (class "Default")
      (node (ref "IC7") (pin "6") (pinfunction "VO_B_6") (pintype "bidirectional"))
      (node (ref "U$2") (pin "S") (pinfunction "OUT_S") (pintype "bidirectional"))
    )
    (net (code "73") (name "Net-(IC7-V_ISO)") (class "Default")
      (node (ref "C7") (pin "2") (pinfunction "2_2") (pintype "passive"))
      (node (ref "IC7") (pin "8") (pinfunction "V_ISO_8") (pintype "bidirectional"))
    )
    (net (code "74") (name "Net-(IC9-Pad+VOUT)") (class "Default")
      (node (ref "IC9") (pin "+VOUT") (pinfunction "+VOUT_+VOUT") (pintype "bidirectional"))
      (node (ref "L1") (pin "1") (pinfunction "1_1") (pintype "passive"))
    )
    (net (code "75") (name "Net-(IC9-Pad-VIN)") (class "Default")
      (node (ref "IC9") (pin "-VIN") (pinfunction "-VIN_-VIN") (pintype "bidirectional"))
      (node (ref "J1") (pin "2") (pinfunction "2_2") (pintype "passive"))
    )
    (net (code "76") (name "Net-(IC10-Pad+VOUT)") (class "Default")
      (node (ref "IC10") (pin "+VOUT") (pinfunction "+VOUT_+VOUT") (pintype "bidirectional"))
      (node (ref "L2") (pin "1") (pinfunction "1_1") (pintype "passive"))
    )
    (net (code "77") (name "Net-(IC10-Pad-VIN)") (class "Default")
      (node (ref "IC10") (pin "-VIN") (pinfunction "-VIN_-VIN") (pintype "bidirectional"))
      (node (ref "J2") (pin "2") (pinfunction "2_2") (pintype "passive"))
    )
    (net (code "78") (name "Net-(IC11-Pad+VOUT)") (class "Default")
      (node (ref "IC11") (pin "+VOUT") (pinfunction "+VOUT_+VOUT") (pintype "bidirectional"))
      (node (ref "L3") (pin "1") (pinfunction "1_1") (pintype "passive"))
    )
    (net (code "79") (name "Net-(IC11-Pad-VIN)") (class "Default")
      (node (ref "IC11") (pin "-VIN") (pinfunction "-VIN_-VIN") (pintype "bidirectional"))
      (node (ref "J3") (pin "2") (pinfunction "2_2") (pintype "passive"))
    )
    (net (code "80") (name "Net-(IC12-2IN)") (class "Default")
      (node (ref "IC12") (pin "5") (pinfunction "2IN_5") (pintype "bidirectional"))
      (node (ref "PORT1") (pin "1") (pinfunction "1_1") (pintype "bidirectional"))
    )
    (net (code "81") (name "Net-(IC12-3IN)") (class "Default")
      (node (ref "IC12") (pin "7") (pinfunction "3IN_7") (pintype "bidirectional"))
      (node (ref "PORT2") (pin "1") (pinfunction "1_1") (pintype "bidirectional"))
    )
    (net (code "82") (name "Net-(IC12-4IN)") (class "Default")
      (node (ref "IC12") (pin "9") (pinfunction "4IN_9") (pintype "bidirectional"))
      (node (ref "PORT3") (pin "1") (pinfunction "1_1") (pintype "bidirectional"))
    )
    (net (code "83") (name "Net-(IC12-5IN)") (class "Default")
      (node (ref "IC12") (pin "11") (pinfunction "5IN_11") (pintype "bidirectional"))
      (node (ref "PORT4") (pin "1") (pinfunction "1_1") (pintype "bidirectional"))
    )
    (net (code "84") (name "Net-(U$3-OUT)") (class "Default")
      (node (ref "R2") (pin "2") (pinfunction "2_2") (pintype "passive"))
      (node (ref "U$3") (pin "S") (pinfunction "OUT_S") (pintype "bidirectional"))
    )
    (net (code "85") (name "Net-(U$4-OUT)") (class "Default")
      (node (ref "R3") (pin "2") (pinfunction "2_2") (pintype "passive"))
      (node (ref "U$4") (pin "S") (pinfunction "OUT_S") (pintype "bidirectional"))
    )
    (net (code "86") (name "Net-(U$8-2)") (class "Default")
      (node (ref "R1") (pin "2") (pinfunction "2_2") (pintype "passive"))
      (node (ref "U$8") (pin "P$2") (pinfunction "2_P$2") (pintype "bidirectional"))
    )
    (net (code "87") (name "VCC") (class "Default")
      (node (ref "C1") (pin "1") (pinfunction "1_1") (pintype "passive"))
      (node (ref "C11") (pin "1") (pinfunction "1_1") (pintype "passive"))
      (node (ref "C12") (pin "2") (pinfunction "2_2") (pintype "passive"))
      (node (ref "C13") (pin "1") (pinfunction "1_1") (pintype "passive"))
      (node (ref "C2") (pin "1") (pinfunction "1_1") (pintype "passive"))
      (node (ref "C3") (pin "1") (pinfunction "1_1") (pintype "passive"))
      (node (ref "C4") (pin "1") (pinfunction "1_1") (pintype "passive"))
      (node (ref "C5") (pin "1") (pinfunction "1_1") (pintype "passive"))
      (node (ref "IC1") (pin "1") (pinfunction "VCC_1") (pintype "bidirectional"))
      (node (ref "IC12") (pin "1") (pinfunction "VCC_1") (pintype "bidirectional"))
      (node (ref "IC2") (pin "1") (pinfunction "VCC_1") (pintype "bidirectional"))
      (node (ref "IC3") (pin "1") (pinfunction "VCC_1") (pintype "bidirectional"))
      (node (ref "IC4") (pin "1") (pinfunction "VCC_1") (pintype "bidirectional"))
      (node (ref "IC5") (pin "1") (pinfunction "VCC_1") (pintype "bidirectional"))
      (node (ref "IC6") (pin "8") (pinfunction "CL1_8") (pintype "bidirectional"))
      (node (ref "IC8") (pin "P$2") (pinfunction "P$2_P$2") (pintype "bidirectional"))
      (node (ref "U$1") (pin "3.3V") (pinfunction "3.3V_3.3V") (pintype "power_in"))
      (node (ref "U$1") (pin "3.3V3") (pinfunction "3.3V_3.3V3") (pintype "power_in"))
    )
    (net (code "88") (name "unconnected-(IC8-PadP$1)") (class "Default")
      (node (ref "IC8") (pin "P$1") (pinfunction "P$1_P$1") (pintype "bidirectional"))
    )
    (net (code "89") (name "unconnected-(IC8-PadP$14)") (class "Default")
      (node (ref "IC8") (pin "P$14") (pinfunction "P$14_P$14") (pintype "bidirectional"))
    )
    (net (code "90") (name "unconnected-(IC8-PadP$16)") (class "Default")
      (node (ref "IC8") (pin "P$16") (pinfunction "P$16_P$16") (pintype "bidirectional"))
    )
    (net (code "91") (name "unconnected-(IC8-PadP$17)") (class "Default")
      (node (ref "IC8") (pin "P$17") (pinfunction "P$17_P$17") (pintype "bidirectional"))
    )
    (net (code "92") (name "unconnected-(IC8-PadP$18)") (class "Default")
      (node (ref "IC8") (pin "P$18") (pinfunction "P$18_P$18") (pintype "bidirectional"))
    )
    (net (code "93") (name "unconnected-(IC8-PadP$20)") (class "Default")
      (node (ref "IC8") (pin "P$20") (pinfunction "P$20_P$20") (pintype "bidirectional"))
    )
    (net (code "94") (name "unconnected-(IC9-PadNC)") (class "Default")
      (node (ref "IC9") (pin "NC") (pinfunction "NC_NC") (pintype "bidirectional"))
    )
    (net (code "95") (name "unconnected-(IC10-PadNC)") (class "Default")
      (node (ref "IC10") (pin "NC") (pinfunction "NC_NC") (pintype "bidirectional"))
    )
    (net (code "96") (name "unconnected-(IC11-PadNC)") (class "Default")
      (node (ref "IC11") (pin "NC") (pinfunction "NC_NC") (pintype "bidirectional"))
    )
    (net (code "97") (name "unconnected-(IC12-1IN-Pad3)") (class "Default")
      (node (ref "IC12") (pin "3") (pinfunction "1IN_3") (pintype "bidirectional"))
    )
    (net (code "98") (name "unconnected-(IC12-1OUT-Pad2)") (class "Default")
      (node (ref "IC12") (pin "2") (pinfunction "1OUT_2") (pintype "bidirectional"))
    )
    (net (code "99") (name "unconnected-(IC12-6IN-Pad14)") (class "Default")
      (node (ref "IC12") (pin "14") (pinfunction "6IN_14") (pintype "bidirectional"))
    )
    (net (code "100") (name "unconnected-(IC12-6OUT-Pad15)") (class "Default")
      (node (ref "IC12") (pin "15") (pinfunction "6OUT_15") (pintype "bidirectional"))
    )
    (net (code "101") (name "unconnected-(IC12-NC-Pad16)") (class "Default")
      (node (ref "IC12") (pin "16") (pinfunction "NC_16") (pintype "bidirectional"))
    )
    (net (code "102") (name "unconnected-(IC12-NC2-Pad13)") (class "Default")
      (node (ref "IC12") (pin "13") (pinfunction "NC2_13") (pintype "bidirectional"))
    )
    (net (code "103") (name "unconnected-(PORT1-Pad2)") (class "Default")
      (node (ref "PORT1") (pin "2") (pinfunction "2_2") (pintype "bidirectional"))
    )
    (net (code "104") (name "unconnected-(PORT1-Pad8)") (class "Default")
      (node (ref "PORT1") (pin "8") (pinfunction "8_8") (pintype "bidirectional"))
    )
    (net (code "105") (name "unconnected-(PORT2-Pad2)") (class "Default")
      (node (ref "PORT2") (pin "2") (pinfunction "2_2") (pintype "bidirectional"))
    )
    (net (code "106") (name "unconnected-(PORT2-Pad8)") (class "Default")
      (node (ref "PORT2") (pin "8") (pinfunction "8_8") (pintype "bidirectional"))
    )
    (net (code "107") (name "unconnected-(PORT3-Pad2)") (class "Default")
      (node (ref "PORT3") (pin "2") (pinfunction "2_2") (pintype "bidirectional"))
    )
    (net (code "108") (name "unconnected-(PORT3-Pad8)") (class "Default")
      (node (ref "PORT3") (pin "8") (pinfunction "8_8") (pintype "bidirectional"))
    )
    (net (code "109") (name "unconnected-(PORT4-Pad2)") (class "Default")
      (node (ref "PORT4") (pin "2") (pinfunction "2_2") (pintype "bidirectional"))
    )
    (net (code "110") (name "unconnected-(PORT4-Pad8)") (class "Default")
      (node (ref "PORT4") (pin "8") (pinfunction "8_8") (pintype "bidirectional"))
    )
    (net (code "111") (name "unconnected-(SERIAL1-Pad5)") (class "Default")
      (node (ref "SERIAL1") (pin "5") (pinfunction "5_5") (pintype "bidirectional"))
    )
    (net (code "112") (name "unconnected-(SERIAL1-Pad6)") (class "Default")
      (node (ref "SERIAL1") (pin "6") (pinfunction "6_6") (pintype "bidirectional"))
    )
    (net (code "113") (name "unconnected-(SERIAL1-Pad7)") (class "Default")
      (node (ref "SERIAL1") (pin "7") (pinfunction "7_7") (pintype "bidirectional"))
    )
    (net (code "114") (name "unconnected-(SERIAL1-Pad8)") (class "Default")
      (node (ref "SERIAL1") (pin "8") (pinfunction "8_8") (pintype "bidirectional"))
    )
    (net (code "115") (name "unconnected-(SERIAL2-Pad5)") (class "Default")
      (node (ref "SERIAL2") (pin "5") (pinfunction "5_5") (pintype "bidirectional"))
    )
    (net (code "116") (name "unconnected-(SERIAL2-Pad6)") (class "Default")
      (node (ref "SERIAL2") (pin "6") (pinfunction "6_6") (pintype "bidirectional"))
    )
    (net (code "117") (name "unconnected-(SERIAL2-Pad7)") (class "Default")
      (node (ref "SERIAL2") (pin "7") (pinfunction "7_7") (pintype "bidirectional"))
    )
    (net (code "118") (name "unconnected-(SERIAL2-Pad8)") (class "Default")
      (node (ref "SERIAL2") (pin "8") (pinfunction "8_8") (pintype "bidirectional"))
    )
    (net (code "119") (name "unconnected-(SERIAL3-Pad7)") (class "Default")
      (node (ref "SERIAL3") (pin "7") (pinfunction "7_7") (pintype "bidirectional"))
    )
    (net (code "120") (name "unconnected-(SERIAL3-Pad8)") (class "Default")
      (node (ref "SERIAL3") (pin "8") (pinfunction "8_8") (pintype "bidirectional"))
    )
    (net (code "121") (name "unconnected-(SERIAL4-Pad7)") (class "Default")
      (node (ref "SERIAL4") (pin "7") (pinfunction "7_7") (pintype "bidirectional"))
    )
    (net (code "122") (name "unconnected-(SERIAL4-Pad8)") (class "Default")
      (node (ref "SERIAL4") (pin "8") (pinfunction "8_8") (pintype "bidirectional"))
    )
    (net (code "123") (name "unconnected-(SERIAL5-Pad7)") (class "Default")
      (node (ref "SERIAL5") (pin "7") (pinfunction "7_7") (pintype "bidirectional"))
    )
    (net (code "124") (name "unconnected-(SERIAL5-Pad8)") (class "Default")
      (node (ref "SERIAL5") (pin "8") (pinfunction "8_8") (pintype "bidirectional"))
    )
    (net (code "125") (name "unconnected-(U$1-11{slash}MOSI0-Pad11)") (class "Default")
      (node (ref "U$1") (pin "11") (pinfunction "11/MOSI0_11") (pintype "bidirectional"))
    )
    (net (code "126") (name "unconnected-(U$1-12{slash}MISO0-Pad12)") (class "Default")
      (node (ref "U$1") (pin "12") (pinfunction "12/MISO0_12") (pintype "bidirectional"))
    )
    (net (code "127") (name "unconnected-(U$1-13{slash}SCK0{slash}LED-Pad13)") (class "Default")
      (node (ref "U$1") (pin "13") (pinfunction "13/SCK0/LED_13") (pintype "bidirectional"))
    )
    (net (code "128") (name "unconnected-(U$1-29{slash}T{slash}PWM-Pad29)") (class "Default")
      (node (ref "U$1") (pin "29") (pinfunction "29/T/PWM_29") (pintype "bidirectional"))
    )
    (net (code "129") (name "unconnected-(U$1-30{slash}T{slash}PWM-Pad30)") (class "Default")
      (node (ref "U$1") (pin "30") (pinfunction "30/T/PWM_30") (pintype "bidirectional"))
    )
    (net (code "130") (name "unconnected-(U$1-A21{slash}DAC0-PadA21)") (class "Default")
      (node (ref "U$1") (pin "A21") (pinfunction "A21/DAC0_A21") (pintype "bidirectional"))
    )
    (net (code "131") (name "unconnected-(U$1-A22{slash}DAC1-PadA22)") (class "Default")
      (node (ref "U$1") (pin "A22") (pinfunction "A22/DAC1_A22") (pintype "bidirectional"))
    )
    (net (code "132") (name "unconnected-(U$1-Pad24)") (class "Default")
      (node (ref "U$1") (pin "24") (pinfunction "24_24") (pintype "bidirectional"))
    )
    (net (code "133") (name "unconnected-(U$1-Pad25)") (class "Default")
      (node (ref "U$1") (pin "25") (pinfunction "25_25") (pintype "bidirectional"))
    )
    (net (code "134") (name "unconnected-(U$1-Pad26)") (class "Default")
      (node (ref "U$1") (pin "26") (pinfunction "26_26") (pintype "bidirectional"))
    )
    (net (code "135") (name "unconnected-(U$1-Pad27)") (class "Default")
      (node (ref "U$1") (pin "27") (pinfunction "27_27") (pintype "bidirectional"))
    )
    (net (code "136") (name "unconnected-(U$1-Pad28)") (class "Default")
      (node (ref "U$1") (pin "28") (pinfunction "28_28") (pintype "bidirectional"))
    )
  )
)
